# uass-antena-side.net
KiCad netlist of a schematic drawn in EAGLE
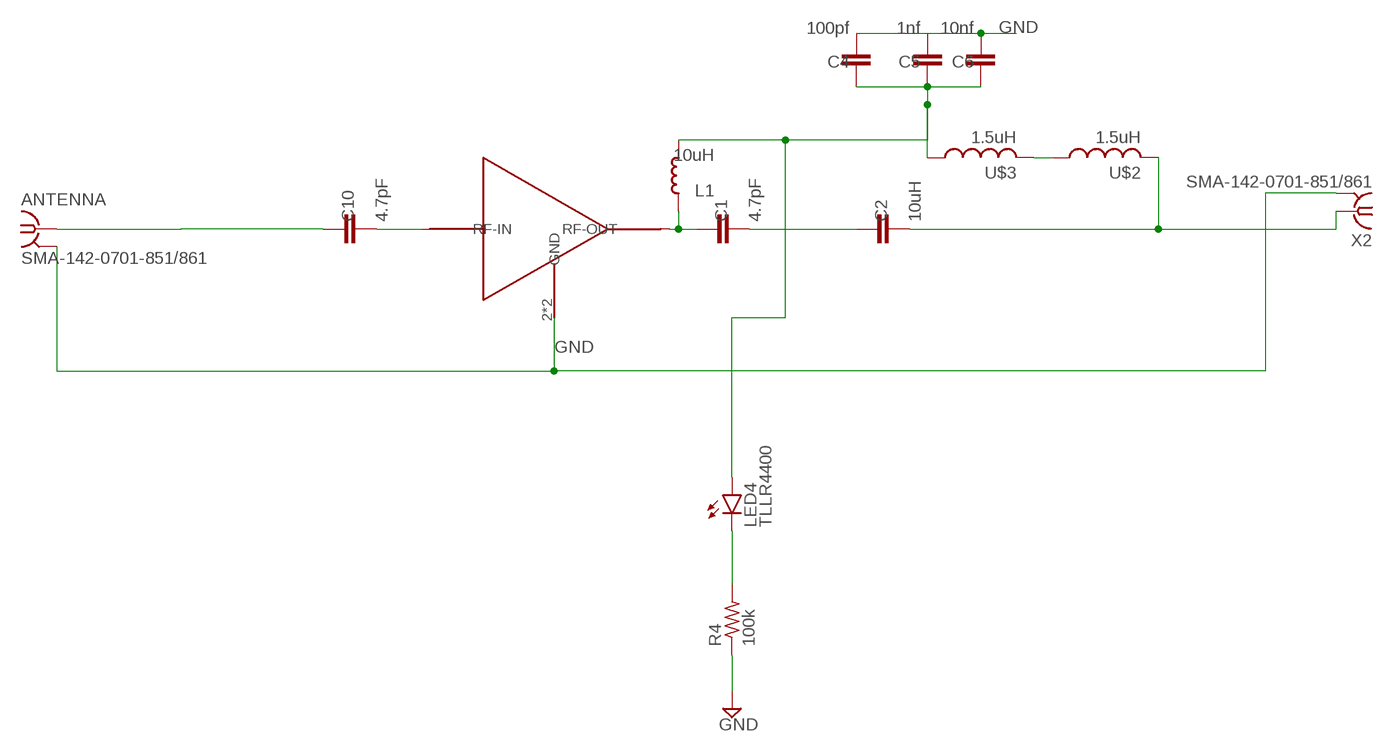
[diagram p0: schematic, sheet 1]

(export (version "E")
  (design (tool "Eeschema 10.0.6"))
  (components
    (comp (ref "ANTENNA")
      (value "SMA-142-0701-851/861")
      (footprint "eagle-import:J502-ND-142-0701-851_861")
      (fields (field (name "MF") "JOHNSON COMPONENTS") (field (name "MPN") "142-0701-851"))
      (libsource (lib "eagle-import") (part "SMA-142-0701-851/861"))
    )
    (comp (ref "C1")
      (value "4.7pF")
      (footprint "eagle-import:0603")
      (libsource (lib "eagle-import") (part "10UF-0603-6.3V-20%"))
    )
    (comp (ref "C2")
      (value "10uH")
      (footprint "eagle-import:0603")
      (libsource (lib "eagle-import") (part "10UF-0603-6.3V-20%"))
    )
    (comp (ref "C4")
      (value "100pf")
      (footprint "eagle-import:0603")
      (libsource (lib "eagle-import") (part "10UF-0603-6.3V-20%"))
    )
    (comp (ref "C5")
      (value "1nf")
      (footprint "eagle-import:0603")
      (libsource (lib "eagle-import") (part "10UF-0603-6.3V-20%"))
    )
    (comp (ref "C6")
      (value "10nf")
      (footprint "eagle-import:0603")
      (libsource (lib "eagle-import") (part "10UF-0603-6.3V-20%"))
    )
    (comp (ref "C10")
      (value "4.7pF")
      (footprint "eagle-import:0603")
      (libsource (lib "eagle-import") (part "10UF-0603-6.3V-20%"))
    )
    (comp (ref "L1")
      (value "10uH")
      (footprint "eagle-import:L0603")
      (libsource (lib "eagle-import") (part "L_0603"))
    )
    (comp (ref "LED4")
      (value "TLLR4400")
      (footprint "eagle-import:LED3MM")
      (fields (field (name "MF") "VISHAY SEMICONDUCTOR"))
      (libsource (lib "eagle-import") (part "TLLR4400"))
    )
    (comp (ref "R4")
      (value "100k")
      (footprint "eagle-import:R0603")
      (libsource (lib "eagle-import") (part "R-US_R0603"))
    )
    (comp (ref "U$1")
      (value "PSA4-5043+")
      (footprint "eagle-import:PSA4-5043+")
      (fields (field (name "MF") "Mini-Circuits"))
      (libsource (lib "eagle-import") (part "PSA4-5043+"))
    )
    (comp (ref "U$2")
      (value "1.5uH")
      (footprint "eagle-import:C0504")
      (libsource (lib "eagle-import") (part "L504"))
    )
    (comp (ref "U$3")
      (value "1.5uH")
      (footprint "eagle-import:C0504")
      (libsource (lib "eagle-import") (part "L504"))
    )
    (comp (ref "X2")
      (value "SMA-142-0701-851/861")
      (footprint "eagle-import:J502-ND-142-0701-851_861")
      (fields (field (name "MF") "JOHNSON COMPONENTS") (field (name "MPN") "142-0701-851"))
      (libsource (lib "eagle-import") (part "SMA-142-0701-851/861"))
    )
  )
  (nets
    (net (code "1") (name "GND") (class "Default")
      (node (ref "ANTENNA") (pin "G@1") (pinfunction "2_G@1") (pintype "passive"))
      (node (ref "ANTENNA") (pin "G@2") (pinfunction "2_G@2") (pintype "passive"))
      (node (ref "ANTENNA") (pin "G@3") (pinfunction "2_G@3") (pintype "passive"))
      (node (ref "ANTENNA") (pin "G@4") (pinfunction "2_G@4") (pintype "passive"))
      (node (ref "C4") (pin "2") (pinfunction "2_2") (pintype "passive"))
      (node (ref "C5") (pin "2") (pinfunction "2_2") (pintype "passive"))
      (node (ref "C6") (pin "2") (pinfunction "2_2") (pintype "passive"))
      (node (ref "R4") (pin "1") (pinfunction "1_1") (pintype "passive"))
      (node (ref "U$1") (pin "2") (pinfunction "GND_2") (pintype "bidirectional"))
      (node (ref "U$1") (pin "4") (pinfunction "GND_4") (pintype "bidirectional"))
      (node (ref "X2") (pin "G@1") (pinfunction "2_G@1") (pintype "passive"))
      (node (ref "X2") (pin "G@2") (pinfunction "2_G@2") (pintype "passive"))
      (node (ref "X2") (pin "G@3") (pinfunction "2_G@3") (pintype "passive"))
      (node (ref "X2") (pin "G@4") (pinfunction "2_G@4") (pintype "passive"))
    )
    (net (code "2") (name "Net-(ANTENNA-Pad1)") (class "Default")
      (node (ref "ANTENNA") (pin "1") (pinfunction "1_1") (pintype "passive"))
      (node (ref "C10") (pin "1") (pinfunction "1_1") (pintype "passive"))
    )
    (net (code "3") (name "Net-(C1-Pad2)") (class "Default")
      (node (ref "C1") (pin "2") (pinfunction "2_2") (pintype "passive"))
      (node (ref "C2") (pin "1") (pinfunction "1_1") (pintype "passive"))
    )
    (net (code "4") (name "Net-(C2-Pad2)") (class "Default")
      (node (ref "C2") (pin "2") (pinfunction "2_2") (pintype "passive"))
      (node (ref "U$2") (pin "2") (pinfunction "2_2") (pintype "passive"))
      (node (ref "X2") (pin "1") (pinfunction "1_1") (pintype "passive"))
    )
    (net (code "5") (name "Net-(C4-Pad1)") (class "Default")
      (node (ref "C4") (pin "1") (pinfunction "1_1") (pintype "passive"))
      (node (ref "C5") (pin "1") (pinfunction "1_1") (pintype "passive"))
      (node (ref "C6") (pin "1") (pinfunction "1_1") (pintype "passive"))
      (node (ref "L1") (pin "1") (pinfunction "1_1") (pintype "passive"))
      (node (ref "LED4") (pin "A") (pinfunction "A_A") (pintype "passive"))
      (node (ref "U$3") (pin "1") (pinfunction "1_1") (pintype "passive"))
    )
    (net (code "6") (name "Net-(LED4-C)") (class "Default")
      (node (ref "LED4") (pin "K") (pinfunction "C_K") (pintype "passive"))
      (node (ref "R4") (pin "2") (pinfunction "2_2") (pintype "passive"))
    )
    (net (code "7") (name "Net-(U$1-RF-IN)") (class "Default")
      (node (ref "C10") (pin "2") (pinfunction "2_2") (pintype "passive"))
      (node (ref "U$1") (pin "3") (pinfunction "RF-IN_3") (pintype "bidirectional"))
    )
    (net (code "8") (name "Net-(U$1-RF-OUT)") (class "Default")
      (node (ref "C1") (pin "1") (pinfunction "1_1") (pintype "passive"))
      (node (ref "L1") (pin "2") (pinfunction "2_2") (pintype "passive"))
      (node (ref "U$1") (pin "1") (pinfunction "RF-OUT_1") (pintype "bidirectional"))
    )
    (net (code "9") (name "Net-(U$2-Pad1)") (class "Default")
      (node (ref "U$2") (pin "1") (pinfunction "1_1") (pintype "passive"))
      (node (ref "U$3") (pin "2") (pinfunction "2_2") (pintype "passive"))
    )
  )
)
